# M220loads.net
KiCad netlist of a schematic drawn in EAGLE
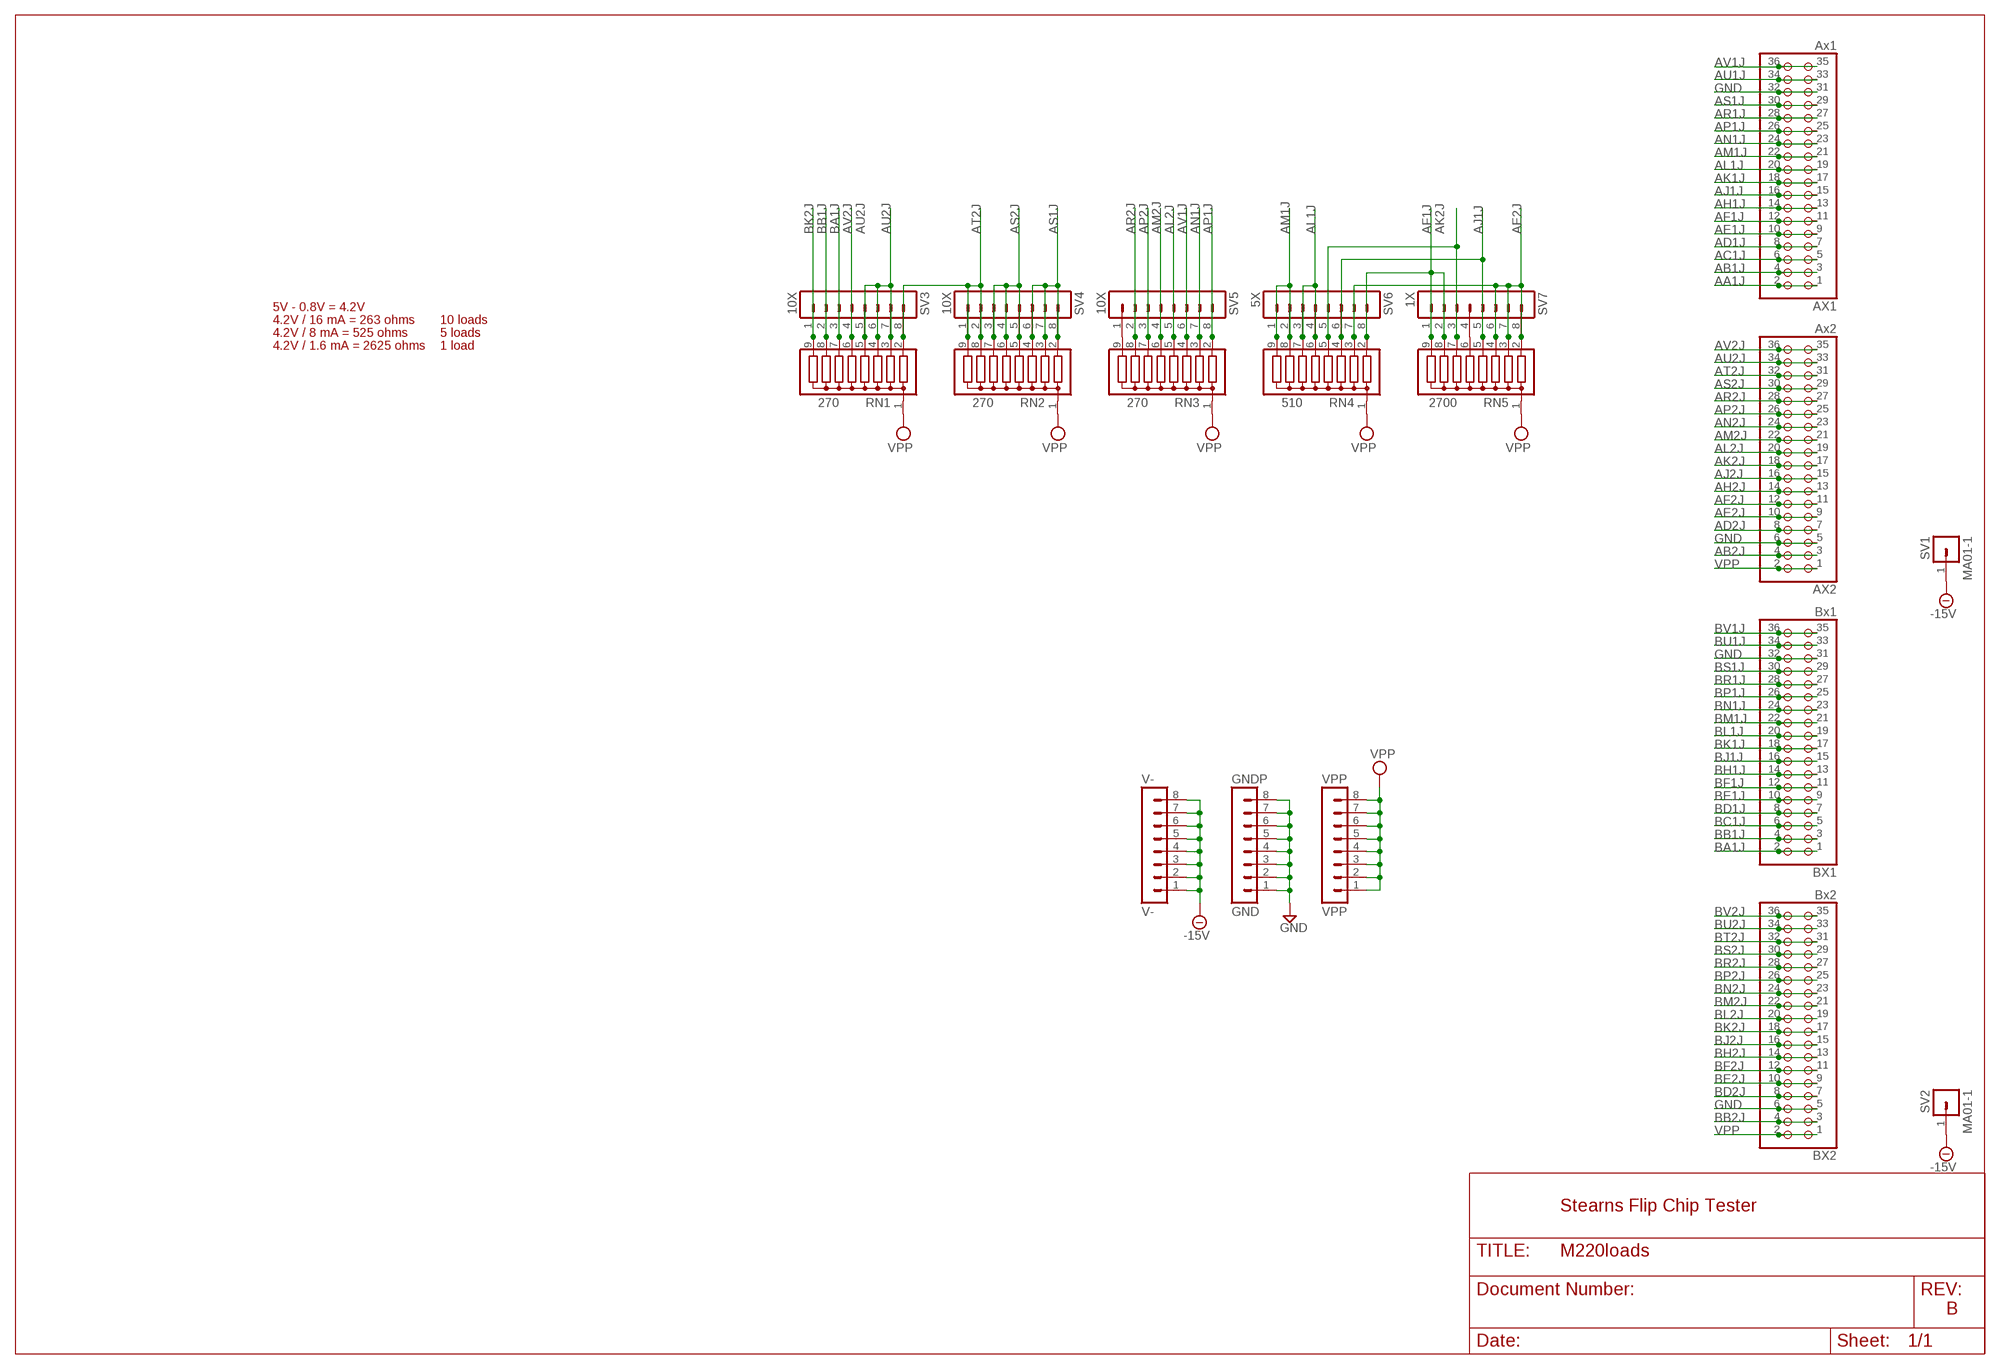
[diagram p0: schematic, sheet 1]

(export (version "E")
  (design (tool "Eeschema 10.0.6"))
  (components
    (comp (ref "AX1")
      (value "Ax1")
      (footprint "eagle-import:2X18")
      (libsource (lib "eagle-import") (part "PINHD-2X18"))
    )
    (comp (ref "AX2")
      (value "Ax2")
      (footprint "eagle-import:2X18")
      (libsource (lib "eagle-import") (part "PINHD-2X18"))
    )
    (comp (ref "BX1")
      (value "Bx1")
      (footprint "eagle-import:2X18")
      (libsource (lib "eagle-import") (part "PINHD-2X18"))
    )
    (comp (ref "BX2")
      (value "Bx2")
      (footprint "eagle-import:2X18")
      (libsource (lib "eagle-import") (part "PINHD-2X18"))
    )
    (comp (ref "GNDP")
      (value "GND")
      (footprint "eagle-import:MA08-1")
      (libsource (lib "eagle-import") (part "MA08-1"))
    )
    (comp (ref "RN1")
      (value "270")
      (footprint "eagle-import:SIL9")
      (libsource (lib "eagle-import") (part "G08R"))
    )
    (comp (ref "RN2")
      (value "270")
      (footprint "eagle-import:SIL9")
      (libsource (lib "eagle-import") (part "G08R"))
    )
    (comp (ref "RN3")
      (value "270")
      (footprint "eagle-import:SIL9")
      (libsource (lib "eagle-import") (part "G08R"))
    )
    (comp (ref "RN4")
      (value "510")
      (footprint "eagle-import:SIL9")
      (libsource (lib "eagle-import") (part "G08R"))
    )
    (comp (ref "RN5")
      (value "2700")
      (footprint "eagle-import:SIL9")
      (libsource (lib "eagle-import") (part "G08R"))
    )
    (comp (ref "SV1")
      (value "MA01-1")
      (footprint "eagle-import:MA01-1")
      (libsource (lib "eagle-import") (part "MA01-1"))
    )
    (comp (ref "SV2")
      (value "MA01-1")
      (footprint "eagle-import:MA01-1")
      (libsource (lib "eagle-import") (part "MA01-1"))
    )
    (comp (ref "SV3")
      (value "10X")
      (footprint "eagle-import:MA08-1")
      (libsource (lib "eagle-import") (part "MA08-1"))
    )
    (comp (ref "SV4")
      (value "10X")
      (footprint "eagle-import:MA08-1")
      (libsource (lib "eagle-import") (part "MA08-1"))
    )
    (comp (ref "SV5")
      (value "10X")
      (footprint "eagle-import:MA08-1")
      (libsource (lib "eagle-import") (part "MA08-1"))
    )
    (comp (ref "SV6")
      (value "5X")
      (footprint "eagle-import:MA08-1")
      (libsource (lib "eagle-import") (part "MA08-1"))
    )
    (comp (ref "SV7")
      (value "1X")
      (footprint "eagle-import:MA08-1")
      (libsource (lib "eagle-import") (part "MA08-1"))
    )
    (comp (ref "V-")
      (value "V-")
      (footprint "eagle-import:MA08-1")
      (libsource (lib "eagle-import") (part "MA08-1"))
    )
    (comp (ref "VPP")
      (value "VPP")
      (footprint "eagle-import:MA08-1")
      (libsource (lib "eagle-import") (part "MA08-1"))
    )
  )
  (nets
    (net (code "1") (name "-15V") (class "Default")
      (node (ref "SV1") (pin "1") (pinfunction "1_1") (pintype "passive"))
      (node (ref "SV2") (pin "1") (pinfunction "1_1") (pintype "passive"))
      (node (ref "V-") (pin "1") (pinfunction "1_1") (pintype "passive"))
      (node (ref "V-") (pin "2") (pinfunction "2_2") (pintype "passive"))
      (node (ref "V-") (pin "3") (pinfunction "3_3") (pintype "passive"))
      (node (ref "V-") (pin "4") (pinfunction "4_4") (pintype "passive"))
      (node (ref "V-") (pin "5") (pinfunction "5_5") (pintype "passive"))
      (node (ref "V-") (pin "6") (pinfunction "6_6") (pintype "passive"))
      (node (ref "V-") (pin "7") (pinfunction "7_7") (pintype "passive"))
      (node (ref "V-") (pin "8") (pinfunction "8_8") (pintype "passive"))
    )
    (net (code "2") (name "/AA1J") (class "Default")
      (node (ref "AX1") (pin "1") (pinfunction "1_1") (pintype "passive"))
      (node (ref "AX1") (pin "2") (pinfunction "2_2") (pintype "passive"))
    )
    (net (code "3") (name "/AB1J") (class "Default")
      (node (ref "AX1") (pin "3") (pinfunction "3_3") (pintype "passive"))
      (node (ref "AX1") (pin "4") (pinfunction "4_4") (pintype "passive"))
    )
    (net (code "4") (name "/AB2J") (class "Default")
      (node (ref "AX2") (pin "3") (pinfunction "3_3") (pintype "passive"))
      (node (ref "AX2") (pin "4") (pinfunction "4_4") (pintype "passive"))
    )
    (net (code "5") (name "/AC1J") (class "Default")
      (node (ref "AX1") (pin "5") (pinfunction "5_5") (pintype "passive"))
      (node (ref "AX1") (pin "6") (pinfunction "6_6") (pintype "passive"))
    )
    (net (code "6") (name "/AD1J") (class "Default")
      (node (ref "AX1") (pin "7") (pinfunction "7_7") (pintype "passive"))
      (node (ref "AX1") (pin "8") (pinfunction "8_8") (pintype "passive"))
    )
    (net (code "7") (name "/AD2J") (class "Default")
      (node (ref "AX2") (pin "7") (pinfunction "7_7") (pintype "passive"))
      (node (ref "AX2") (pin "8") (pinfunction "8_8") (pintype "passive"))
    )
    (net (code "8") (name "/AE1J") (class "Default")
      (node (ref "AX1") (pin "10") (pinfunction "10_10") (pintype "passive"))
      (node (ref "AX1") (pin "9") (pinfunction "9_9") (pintype "passive"))
    )
    (net (code "9") (name "/AE2J") (class "Default")
      (node (ref "AX2") (pin "10") (pinfunction "10_10") (pintype "passive"))
      (node (ref "AX2") (pin "9") (pinfunction "9_9") (pintype "passive"))
      (node (ref "RN4") (pin "3") (pinfunction "3_3") (pintype "passive"))
      (node (ref "RN5") (pin "2") (pinfunction "2_2") (pintype "passive"))
      (node (ref "RN5") (pin "3") (pinfunction "3_3") (pintype "passive"))
      (node (ref "RN5") (pin "4") (pinfunction "4_4") (pintype "passive"))
      (node (ref "SV6") (pin "7") (pinfunction "7_7") (pintype "passive"))
      (node (ref "SV7") (pin "6") (pinfunction "6_6") (pintype "passive"))
      (node (ref "SV7") (pin "7") (pinfunction "7_7") (pintype "passive"))
      (node (ref "SV7") (pin "8") (pinfunction "8_8") (pintype "passive"))
    )
    (net (code "10") (name "/AF1J") (class "Default")
      (node (ref "AX1") (pin "11") (pinfunction "11_11") (pintype "passive"))
      (node (ref "AX1") (pin "12") (pinfunction "12_12") (pintype "passive"))
      (node (ref "RN4") (pin "2") (pinfunction "2_2") (pintype "passive"))
      (node (ref "RN5") (pin "8") (pinfunction "8_8") (pintype "passive"))
      (node (ref "RN5") (pin "9") (pinfunction "9_9") (pintype "passive"))
      (node (ref "SV6") (pin "8") (pinfunction "8_8") (pintype "passive"))
      (node (ref "SV7") (pin "1") (pinfunction "1_1") (pintype "passive"))
      (node (ref "SV7") (pin "2") (pinfunction "2_2") (pintype "passive"))
    )
    (net (code "11") (name "/AF2J") (class "Default")
      (node (ref "AX2") (pin "11") (pinfunction "11_11") (pintype "passive"))
      (node (ref "AX2") (pin "12") (pinfunction "12_12") (pintype "passive"))
    )
    (net (code "12") (name "/AH1J") (class "Default")
      (node (ref "AX1") (pin "13") (pinfunction "13_13") (pintype "passive"))
      (node (ref "AX1") (pin "14") (pinfunction "14_14") (pintype "passive"))
    )
    (net (code "13") (name "/AH2J") (class "Default")
      (node (ref "AX2") (pin "13") (pinfunction "13_13") (pintype "passive"))
      (node (ref "AX2") (pin "14") (pinfunction "14_14") (pintype "passive"))
    )
    (net (code "14") (name "/AJ1J") (class "Default")
      (node (ref "AX1") (pin "15") (pinfunction "15_15") (pintype "passive"))
      (node (ref "AX1") (pin "16") (pinfunction "16_16") (pintype "passive"))
      (node (ref "RN4") (pin "4") (pinfunction "4_4") (pintype "passive"))
      (node (ref "RN5") (pin "5") (pinfunction "5_5") (pintype "passive"))
      (node (ref "SV6") (pin "6") (pinfunction "6_6") (pintype "passive"))
      (node (ref "SV7") (pin "5") (pinfunction "5_5") (pintype "passive"))
    )
    (net (code "15") (name "/AJ2J") (class "Default")
      (node (ref "AX2") (pin "15") (pinfunction "15_15") (pintype "passive"))
      (node (ref "AX2") (pin "16") (pinfunction "16_16") (pintype "passive"))
    )
    (net (code "16") (name "/AK1J") (class "Default")
      (node (ref "AX1") (pin "17") (pinfunction "17_17") (pintype "passive"))
      (node (ref "AX1") (pin "18") (pinfunction "18_18") (pintype "passive"))
    )
    (net (code "17") (name "/AK2J") (class "Default")
      (node (ref "AX2") (pin "17") (pinfunction "17_17") (pintype "passive"))
      (node (ref "AX2") (pin "18") (pinfunction "18_18") (pintype "passive"))
      (node (ref "RN4") (pin "5") (pinfunction "5_5") (pintype "passive"))
      (node (ref "RN5") (pin "7") (pinfunction "7_7") (pintype "passive"))
      (node (ref "SV6") (pin "5") (pinfunction "5_5") (pintype "passive"))
      (node (ref "SV7") (pin "3") (pinfunction "3_3") (pintype "passive"))
    )
    (net (code "18") (name "/AL1J") (class "Default")
      (node (ref "AX1") (pin "19") (pinfunction "19_19") (pintype "passive"))
      (node (ref "AX1") (pin "20") (pinfunction "20_20") (pintype "passive"))
      (node (ref "RN4") (pin "6") (pinfunction "6_6") (pintype "passive"))
      (node (ref "RN4") (pin "7") (pinfunction "7_7") (pintype "passive"))
      (node (ref "SV6") (pin "3") (pinfunction "3_3") (pintype "passive"))
      (node (ref "SV6") (pin "4") (pinfunction "4_4") (pintype "passive"))
    )
    (net (code "19") (name "/AL2J") (class "Default")
      (node (ref "AX2") (pin "19") (pinfunction "19_19") (pintype "passive"))
      (node (ref "AX2") (pin "20") (pinfunction "20_20") (pintype "passive"))
      (node (ref "RN3") (pin "5") (pinfunction "5_5") (pintype "passive"))
      (node (ref "SV5") (pin "5") (pinfunction "5_5") (pintype "passive"))
    )
    (net (code "20") (name "/AM1J") (class "Default")
      (node (ref "AX1") (pin "21") (pinfunction "21_21") (pintype "passive"))
      (node (ref "AX1") (pin "22") (pinfunction "22_22") (pintype "passive"))
      (node (ref "RN4") (pin "8") (pinfunction "8_8") (pintype "passive"))
      (node (ref "RN4") (pin "9") (pinfunction "9_9") (pintype "passive"))
      (node (ref "SV6") (pin "1") (pinfunction "1_1") (pintype "passive"))
      (node (ref "SV6") (pin "2") (pinfunction "2_2") (pintype "passive"))
    )
    (net (code "21") (name "/AM2J") (class "Default")
      (node (ref "AX2") (pin "21") (pinfunction "21_21") (pintype "passive"))
      (node (ref "AX2") (pin "22") (pinfunction "22_22") (pintype "passive"))
      (node (ref "RN3") (pin "6") (pinfunction "6_6") (pintype "passive"))
      (node (ref "SV5") (pin "4") (pinfunction "4_4") (pintype "passive"))
    )
    (net (code "22") (name "/AN1J") (class "Default")
      (node (ref "AX1") (pin "23") (pinfunction "23_23") (pintype "passive"))
      (node (ref "AX1") (pin "24") (pinfunction "24_24") (pintype "passive"))
      (node (ref "RN3") (pin "3") (pinfunction "3_3") (pintype "passive"))
      (node (ref "SV5") (pin "7") (pinfunction "7_7") (pintype "passive"))
    )
    (net (code "23") (name "/AN2J") (class "Default")
      (node (ref "AX2") (pin "23") (pinfunction "23_23") (pintype "passive"))
      (node (ref "AX2") (pin "24") (pinfunction "24_24") (pintype "passive"))
    )
    (net (code "24") (name "/AP1J") (class "Default")
      (node (ref "AX1") (pin "25") (pinfunction "25_25") (pintype "passive"))
      (node (ref "AX1") (pin "26") (pinfunction "26_26") (pintype "passive"))
      (node (ref "RN3") (pin "2") (pinfunction "2_2") (pintype "passive"))
      (node (ref "SV5") (pin "8") (pinfunction "8_8") (pintype "passive"))
    )
    (net (code "25") (name "/AP2J") (class "Default")
      (node (ref "AX2") (pin "25") (pinfunction "25_25") (pintype "passive"))
      (node (ref "AX2") (pin "26") (pinfunction "26_26") (pintype "passive"))
      (node (ref "RN3") (pin "7") (pinfunction "7_7") (pintype "passive"))
      (node (ref "SV5") (pin "3") (pinfunction "3_3") (pintype "passive"))
    )
    (net (code "26") (name "/AR1J") (class "Default")
      (node (ref "AX1") (pin "27") (pinfunction "27_27") (pintype "passive"))
      (node (ref "AX1") (pin "28") (pinfunction "28_28") (pintype "passive"))
    )
    (net (code "27") (name "/AR2J") (class "Default")
      (node (ref "AX2") (pin "27") (pinfunction "27_27") (pintype "passive"))
      (node (ref "AX2") (pin "28") (pinfunction "28_28") (pintype "passive"))
      (node (ref "RN3") (pin "8") (pinfunction "8_8") (pintype "passive"))
      (node (ref "SV5") (pin "2") (pinfunction "2_2") (pintype "passive"))
    )
    (net (code "28") (name "/AS1J") (class "Default")
      (node (ref "AX1") (pin "29") (pinfunction "29_29") (pintype "passive"))
      (node (ref "AX1") (pin "30") (pinfunction "30_30") (pintype "passive"))
      (node (ref "RN2") (pin "2") (pinfunction "2_2") (pintype "passive"))
      (node (ref "RN2") (pin "3") (pinfunction "3_3") (pintype "passive"))
      (node (ref "RN2") (pin "4") (pinfunction "4_4") (pintype "passive"))
      (node (ref "SV4") (pin "6") (pinfunction "6_6") (pintype "passive"))
      (node (ref "SV4") (pin "7") (pinfunction "7_7") (pintype "passive"))
      (node (ref "SV4") (pin "8") (pinfunction "8_8") (pintype "passive"))
    )
    (net (code "29") (name "/AS2J") (class "Default")
      (node (ref "AX2") (pin "29") (pinfunction "29_29") (pintype "passive"))
      (node (ref "AX2") (pin "30") (pinfunction "30_30") (pintype "passive"))
      (node (ref "RN2") (pin "5") (pinfunction "5_5") (pintype "passive"))
      (node (ref "RN2") (pin "6") (pinfunction "6_6") (pintype "passive"))
      (node (ref "RN2") (pin "7") (pinfunction "7_7") (pintype "passive"))
      (node (ref "SV4") (pin "3") (pinfunction "3_3") (pintype "passive"))
      (node (ref "SV4") (pin "4") (pinfunction "4_4") (pintype "passive"))
      (node (ref "SV4") (pin "5") (pinfunction "5_5") (pintype "passive"))
    )
    (net (code "30") (name "/AT2J") (class "Default")
      (node (ref "AX2") (pin "31") (pinfunction "31_31") (pintype "passive"))
      (node (ref "AX2") (pin "32") (pinfunction "32_32") (pintype "passive"))
      (node (ref "RN1") (pin "2") (pinfunction "2_2") (pintype "passive"))
      (node (ref "RN2") (pin "8") (pinfunction "8_8") (pintype "passive"))
      (node (ref "RN2") (pin "9") (pinfunction "9_9") (pintype "passive"))
      (node (ref "SV3") (pin "8") (pinfunction "8_8") (pintype "passive"))
      (node (ref "SV4") (pin "1") (pinfunction "1_1") (pintype "passive"))
      (node (ref "SV4") (pin "2") (pinfunction "2_2") (pintype "passive"))
    )
    (net (code "31") (name "/AU1J") (class "Default")
      (node (ref "AX1") (pin "33") (pinfunction "33_33") (pintype "passive"))
      (node (ref "AX1") (pin "34") (pinfunction "34_34") (pintype "passive"))
    )
    (net (code "32") (name "/AU2J") (class "Default")
      (node (ref "AX2") (pin "33") (pinfunction "33_33") (pintype "passive"))
      (node (ref "AX2") (pin "34") (pinfunction "34_34") (pintype "passive"))
      (node (ref "RN1") (pin "3") (pinfunction "3_3") (pintype "passive"))
      (node (ref "RN1") (pin "4") (pinfunction "4_4") (pintype "passive"))
      (node (ref "RN1") (pin "5") (pinfunction "5_5") (pintype "passive"))
      (node (ref "SV3") (pin "5") (pinfunction "5_5") (pintype "passive"))
      (node (ref "SV3") (pin "6") (pinfunction "6_6") (pintype "passive"))
      (node (ref "SV3") (pin "7") (pinfunction "7_7") (pintype "passive"))
    )
    (net (code "33") (name "/AV1J") (class "Default")
      (node (ref "AX1") (pin "35") (pinfunction "35_35") (pintype "passive"))
      (node (ref "AX1") (pin "36") (pinfunction "36_36") (pintype "passive"))
      (node (ref "RN3") (pin "4") (pinfunction "4_4") (pintype "passive"))
      (node (ref "SV5") (pin "6") (pinfunction "6_6") (pintype "passive"))
    )
    (net (code "34") (name "/AV2J") (class "Default")
      (node (ref "AX2") (pin "35") (pinfunction "35_35") (pintype "passive"))
      (node (ref "AX2") (pin "36") (pinfunction "36_36") (pintype "passive"))
      (node (ref "RN1") (pin "6") (pinfunction "6_6") (pintype "passive"))
      (node (ref "SV3") (pin "4") (pinfunction "4_4") (pintype "passive"))
    )
    (net (code "35") (name "/BA1J") (class "Default")
      (node (ref "BX1") (pin "1") (pinfunction "1_1") (pintype "passive"))
      (node (ref "BX1") (pin "2") (pinfunction "2_2") (pintype "passive"))
      (node (ref "RN1") (pin "7") (pinfunction "7_7") (pintype "passive"))
      (node (ref "SV3") (pin "3") (pinfunction "3_3") (pintype "passive"))
    )
    (net (code "36") (name "/BB1J") (class "Default")
      (node (ref "BX1") (pin "3") (pinfunction "3_3") (pintype "passive"))
      (node (ref "BX1") (pin "4") (pinfunction "4_4") (pintype "passive"))
      (node (ref "RN1") (pin "8") (pinfunction "8_8") (pintype "passive"))
      (node (ref "SV3") (pin "2") (pinfunction "2_2") (pintype "passive"))
    )
    (net (code "37") (name "/BB2J") (class "Default")
      (node (ref "BX2") (pin "3") (pinfunction "3_3") (pintype "passive"))
      (node (ref "BX2") (pin "4") (pinfunction "4_4") (pintype "passive"))
    )
    (net (code "38") (name "/BC1J") (class "Default")
      (node (ref "BX1") (pin "5") (pinfunction "5_5") (pintype "passive"))
      (node (ref "BX1") (pin "6") (pinfunction "6_6") (pintype "passive"))
    )
    (net (code "39") (name "/BD1J") (class "Default")
      (node (ref "BX1") (pin "7") (pinfunction "7_7") (pintype "passive"))
      (node (ref "BX1") (pin "8") (pinfunction "8_8") (pintype "passive"))
    )
    (net (code "40") (name "/BD2J") (class "Default")
      (node (ref "BX2") (pin "7") (pinfunction "7_7") (pintype "passive"))
      (node (ref "BX2") (pin "8") (pinfunction "8_8") (pintype "passive"))
    )
    (net (code "41") (name "/BE1J") (class "Default")
      (node (ref "BX1") (pin "10") (pinfunction "10_10") (pintype "passive"))
      (node (ref "BX1") (pin "9") (pinfunction "9_9") (pintype "passive"))
    )
    (net (code "42") (name "/BE2J") (class "Default")
      (node (ref "BX2") (pin "10") (pinfunction "10_10") (pintype "passive"))
      (node (ref "BX2") (pin "9") (pinfunction "9_9") (pintype "passive"))
    )
    (net (code "43") (name "/BF1J") (class "Default")
      (node (ref "BX1") (pin "11") (pinfunction "11_11") (pintype "passive"))
      (node (ref "BX1") (pin "12") (pinfunction "12_12") (pintype "passive"))
    )
    (net (code "44") (name "/BF2J") (class "Default")
      (node (ref "BX2") (pin "11") (pinfunction "11_11") (pintype "passive"))
      (node (ref "BX2") (pin "12") (pinfunction "12_12") (pintype "passive"))
    )
    (net (code "45") (name "/BH1J") (class "Default")
      (node (ref "BX1") (pin "13") (pinfunction "13_13") (pintype "passive"))
      (node (ref "BX1") (pin "14") (pinfunction "14_14") (pintype "passive"))
    )
    (net (code "46") (name "/BH2J") (class "Default")
      (node (ref "BX2") (pin "13") (pinfunction "13_13") (pintype "passive"))
      (node (ref "BX2") (pin "14") (pinfunction "14_14") (pintype "passive"))
    )
    (net (code "47") (name "/BJ1J") (class "Default")
      (node (ref "BX1") (pin "15") (pinfunction "15_15") (pintype "passive"))
      (node (ref "BX1") (pin "16") (pinfunction "16_16") (pintype "passive"))
    )
    (net (code "48") (name "/BJ2J") (class "Default")
      (node (ref "BX2") (pin "15") (pinfunction "15_15") (pintype "passive"))
      (node (ref "BX2") (pin "16") (pinfunction "16_16") (pintype "passive"))
    )
    (net (code "49") (name "/BK1J") (class "Default")
      (node (ref "BX1") (pin "17") (pinfunction "17_17") (pintype "passive"))
      (node (ref "BX1") (pin "18") (pinfunction "18_18") (pintype "passive"))
    )
    (net (code "50") (name "/BK2J") (class "Default")
      (node (ref "BX2") (pin "17") (pinfunction "17_17") (pintype "passive"))
      (node (ref "BX2") (pin "18") (pinfunction "18_18") (pintype "passive"))
      (node (ref "RN1") (pin "9") (pinfunction "9_9") (pintype "passive"))
      (node (ref "SV3") (pin "1") (pinfunction "1_1") (pintype "passive"))
    )
    (net (code "51") (name "/BL1J") (class "Default")
      (node (ref "BX1") (pin "19") (pinfunction "19_19") (pintype "passive"))
      (node (ref "BX1") (pin "20") (pinfunction "20_20") (pintype "passive"))
    )
    (net (code "52") (name "/BL2J") (class "Default")
      (node (ref "BX2") (pin "19") (pinfunction "19_19") (pintype "passive"))
      (node (ref "BX2") (pin "20") (pinfunction "20_20") (pintype "passive"))
    )
    (net (code "53") (name "/BM1J") (class "Default")
      (node (ref "BX1") (pin "21") (pinfunction "21_21") (pintype "passive"))
      (node (ref "BX1") (pin "22") (pinfunction "22_22") (pintype "passive"))
    )
    (net (code "54") (name "/BM2J") (class "Default")
      (node (ref "BX2") (pin "21") (pinfunction "21_21") (pintype "passive"))
      (node (ref "BX2") (pin "22") (pinfunction "22_22") (pintype "passive"))
    )
    (net (code "55") (name "/BN1J") (class "Default")
      (node (ref "BX1") (pin "23") (pinfunction "23_23") (pintype "passive"))
      (node (ref "BX1") (pin "24") (pinfunction "24_24") (pintype "passive"))
    )
    (net (code "56") (name "/BN2J") (class "Default")
      (node (ref "BX2") (pin "23") (pinfunction "23_23") (pintype "passive"))
      (node (ref "BX2") (pin "24") (pinfunction "24_24") (pintype "passive"))
    )
    (net (code "57") (name "/BP1J") (class "Default")
      (node (ref "BX1") (pin "25") (pinfunction "25_25") (pintype "passive"))
      (node (ref "BX1") (pin "26") (pinfunction "26_26") (pintype "passive"))
    )
    (net (code "58") (name "/BP2J") (class "Default")
      (node (ref "BX2") (pin "25") (pinfunction "25_25") (pintype "passive"))
      (node (ref "BX2") (pin "26") (pinfunction "26_26") (pintype "passive"))
    )
    (net (code "59") (name "/BR1J") (class "Default")
      (node (ref "BX1") (pin "27") (pinfunction "27_27") (pintype "passive"))
      (node (ref "BX1") (pin "28") (pinfunction "28_28") (pintype "passive"))
    )
    (net (code "60") (name "/BR2J") (class "Default")
      (node (ref "BX2") (pin "27") (pinfunction "27_27") (pintype "passive"))
      (node (ref "BX2") (pin "28") (pinfunction "28_28") (pintype "passive"))
    )
    (net (code "61") (name "/BS1J") (class "Default")
      (node (ref "BX1") (pin "29") (pinfunction "29_29") (pintype "passive"))
      (node (ref "BX1") (pin "30") (pinfunction "30_30") (pintype "passive"))
    )
    (net (code "62") (name "/BS2J") (class "Default")
      (node (ref "BX2") (pin "29") (pinfunction "29_29") (pintype "passive"))
      (node (ref "BX2") (pin "30") (pinfunction "30_30") (pintype "passive"))
    )
    (net (code "63") (name "/BT2J") (class "Default")
      (node (ref "BX2") (pin "31") (pinfunction "31_31") (pintype "passive"))
      (node (ref "BX2") (pin "32") (pinfunction "32_32") (pintype "passive"))
    )
    (net (code "64") (name "/BU1J") (class "Default")
      (node (ref "BX1") (pin "33") (pinfunction "33_33") (pintype "passive"))
      (node (ref "BX1") (pin "34") (pinfunction "34_34") (pintype "passive"))
    )
    (net (code "65") (name "/BU2J") (class "Default")
      (node (ref "BX2") (pin "33") (pinfunction "33_33") (pintype "passive"))
      (node (ref "BX2") (pin "34") (pinfunction "34_34") (pintype "passive"))
    )
    (net (code "66") (name "/BV1J") (class "Default")
      (node (ref "BX1") (pin "35") (pinfunction "35_35") (pintype "passive"))
      (node (ref "BX1") (pin "36") (pinfunction "36_36") (pintype "passive"))
    )
    (net (code "67") (name "/BV2J") (class "Default")
      (node (ref "BX2") (pin "35") (pinfunction "35_35") (pintype "passive"))
      (node (ref "BX2") (pin "36") (pinfunction "36_36") (pintype "passive"))
    )
    (net (code "68") (name "GND") (class "Default")
      (node (ref "AX1") (pin "31") (pinfunction "31_31") (pintype "passive"))
      (node (ref "AX1") (pin "32") (pinfunction "32_32") (pintype "passive"))
      (node (ref "AX2") (pin "5") (pinfunction "5_5") (pintype "passive"))
      (node (ref "AX2") (pin "6") (pinfunction "6_6") (pintype "passive"))
      (node (ref "BX1") (pin "31") (pinfunction "31_31") (pintype "passive"))
      (node (ref "BX1") (pin "32") (pinfunction "32_32") (pintype "passive"))
      (node (ref "BX2") (pin "5") (pinfunction "5_5") (pintype "passive"))
      (node (ref "BX2") (pin "6") (pinfunction "6_6") (pintype "passive"))
      (node (ref "GNDP") (pin "1") (pinfunction "1_1") (pintype "passive"))
      (node (ref "GNDP") (pin "2") (pinfunction "2_2") (pintype "passive"))
      (node (ref "GNDP") (pin "3") (pinfunction "3_3") (pintype "passive"))
      (node (ref "GNDP") (pin "4") (pinfunction "4_4") (pintype "passive"))
      (node (ref "GNDP") (pin "5") (pinfunction "5_5") (pintype "passive"))
      (node (ref "GNDP") (pin "6") (pinfunction "6_6") (pintype "passive"))
      (node (ref "GNDP") (pin "7") (pinfunction "7_7") (pintype "passive"))
      (node (ref "GNDP") (pin "8") (pinfunction "8_8") (pintype "passive"))
    )
    (net (code "69") (name "Net-(RN3-Pad9)") (class "Default")
      (node (ref "RN3") (pin "9") (pinfunction "9_9") (pintype "passive"))
      (node (ref "SV5") (pin "1") (pinfunction "1_1") (pintype "passive"))
    )
    (net (code "70") (name "Net-(RN5-Pad6)") (class "Default")
      (node (ref "RN5") (pin "6") (pinfunction "6_6") (pintype "passive"))
      (node (ref "SV7") (pin "4") (pinfunction "4_4") (pintype "passive"))
    )
    (net (code "71") (name "VPP") (class "Default")
      (node (ref "AX2") (pin "1") (pinfunction "1_1") (pintype "passive"))
      (node (ref "AX2") (pin "2") (pinfunction "2_2") (pintype "passive"))
      (node (ref "BX2") (pin "1") (pinfunction "1_1") (pintype "passive"))
      (node (ref "BX2") (pin "2") (pinfunction "2_2") (pintype "passive"))
      (node (ref "RN1") (pin "1") (pinfunction "1_1") (pintype "passive"))
      (node (ref "RN2") (pin "1") (pinfunction "1_1") (pintype "passive"))
      (node (ref "RN3") (pin "1") (pinfunction "1_1") (pintype "passive"))
      (node (ref "RN4") (pin "1") (pinfunction "1_1") (pintype "passive"))
      (node (ref "RN5") (pin "1") (pinfunction "1_1") (pintype "passive"))
      (node (ref "VPP") (pin "1") (pinfunction "1_1") (pintype "passive"))
      (node (ref "VPP") (pin "2") (pinfunction "2_2") (pintype "passive"))
      (node (ref "VPP") (pin "3") (pinfunction "3_3") (pintype "passive"))
      (node (ref "VPP") (pin "4") (pinfunction "4_4") (pintype "passive"))
      (node (ref "VPP") (pin "5") (pinfunction "5_5") (pintype "passive"))
      (node (ref "VPP") (pin "6") (pinfunction "6_6") (pintype "passive"))
      (node (ref "VPP") (pin "7") (pinfunction "7_7") (pintype "passive"))
      (node (ref "VPP") (pin "8") (pinfunction "8_8") (pintype "passive"))
    )
  )
)
